# siren_cutdown.net
KiCad netlist of a schematic drawn in EAGLE
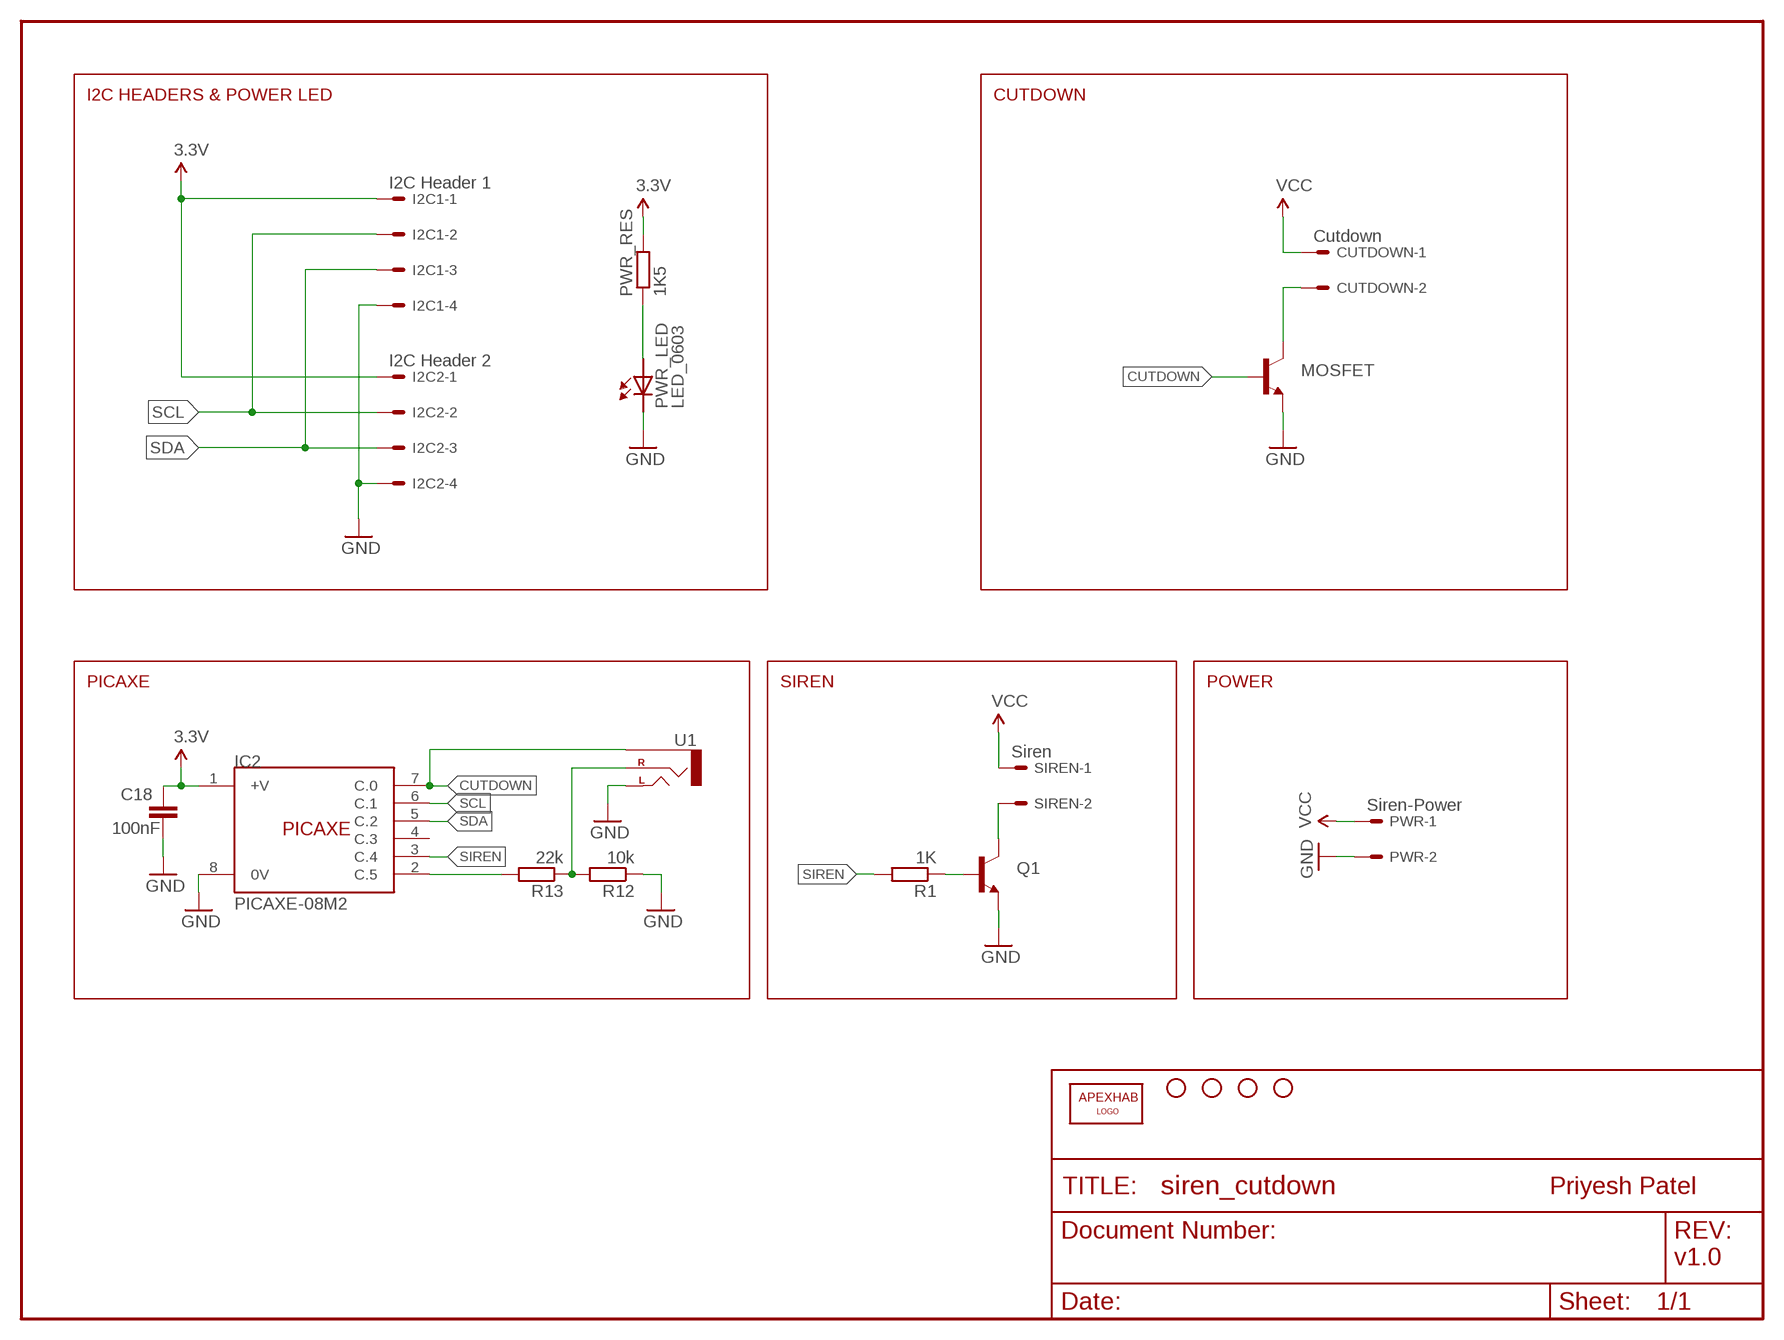
[diagram p0: schematic, sheet 1]

(export (version "E")
  (design (tool "Eeschema 10.0.6"))
  (components
    (comp (ref "C18")
      (value "100nF")
      (footprint "eagle-import:C0805")
      (libsource (lib "eagle-import") (part "C-EUC0805"))
    )
    (comp (ref "CUTDOWN")
      (value "Cutdown")
      (footprint "eagle-import:6410-02")
      (libsource (lib "eagle-import") (part "22-?-0227-2021"))
    )
    (comp (ref "I2C1")
      (value "I2C Header 1")
      (footprint "eagle-import:6410-04")
      (libsource (lib "eagle-import") (part "22-?-0427-2041"))
    )
    (comp (ref "I2C2")
      (value "I2C Header 2")
      (footprint "eagle-import:6410-04")
      (libsource (lib "eagle-import") (part "22-?-0427-2041"))
    )
    (comp (ref "IC2")
      (value "PICAXE-08M2")
      (footprint "eagle-import:SOIC8")
      (libsource (lib "eagle-import") (part "PICAXE-08M2"))
    )
    (comp (ref "JP1")
      (value "APEXHAB-LOGO_APEXHAB-SMALL")
      (footprint "eagle-import:APEXHAB-LOGO-SMALL")
      (libsource (lib "eagle-import") (part "APEXHAB-LOGO_APEXHAB-SMALL"))
    )
    (comp (ref "JP2")
      (value "STAND-OFF")
      (footprint "eagle-import:STAND-OFF")
      (libsource (lib "eagle-import") (part "STAND-OFF"))
    )
    (comp (ref "JP3")
      (value "STAND-OFF")
      (footprint "eagle-import:STAND-OFF")
      (libsource (lib "eagle-import") (part "STAND-OFF"))
    )
    (comp (ref "JP4")
      (value "STAND-OFF")
      (footprint "eagle-import:STAND-OFF")
      (libsource (lib "eagle-import") (part "STAND-OFF"))
    )
    (comp (ref "JP5")
      (value "STAND-OFF")
      (footprint "eagle-import:STAND-OFF")
      (libsource (lib "eagle-import") (part "STAND-OFF"))
    )
    (comp (ref "MOSFET")
      (value "TRANSISTOR_NPNSOT23")
      (footprint "eagle-import:SOT23")
      (libsource (lib "eagle-import") (part "TRANSISTOR_NPNSOT23"))
    )
    (comp (ref "PWR")
      (value "Siren-Power")
      (footprint "eagle-import:6410-02")
      (libsource (lib "eagle-import") (part "22-?-0227-2021"))
    )
    (comp (ref "PWR_LED")
      (value "LED_0603")
      (footprint "eagle-import:CHIPLED_0603")
      (libsource (lib "eagle-import") (part "LED_0603"))
    )
    (comp (ref "PWR_RES")
      (value "1K5")
      (footprint "eagle-import:R0805")
      (libsource (lib "eagle-import") (part "R-EU_R0805"))
    )
    (comp (ref "Q1")
      (value "TRANSISTOR_NPN\"")
      (footprint "eagle-import:SOT223")
      (libsource (lib "eagle-import") (part "TRANSISTOR_NPN{dblquote}"))
    )
    (comp (ref "R1")
      (value "1K")
      (footprint "eagle-import:R0805")
      (libsource (lib "eagle-import") (part "R-EU_R0805"))
    )
    (comp (ref "R12")
      (value "10k")
      (footprint "eagle-import:R0805")
      (libsource (lib "eagle-import") (part "R-EU_R0805"))
    )
    (comp (ref "R13")
      (value "22k")
      (footprint "eagle-import:R0805")
      (libsource (lib "eagle-import") (part "R-EU_R0805"))
    )
    (comp (ref "SIREN")
      (value "Siren")
      (footprint "eagle-import:6410-02")
      (libsource (lib "eagle-import") (part "22-?-0227-2021"))
    )
    (comp (ref "U1")
      (value "AUDIO-JACKPTH")
      (footprint "eagle-import:AUDIO-JACK")
      (libsource (lib "eagle-import") (part "AUDIO-JACKPTH"))
    )
  )
  (nets
    (net (code "1") (name "3.3V") (class "Default")
      (node (ref "C18") (pin "1") (pinfunction "1_1") (pintype "passive"))
      (node (ref "I2C1") (pin "1") (pinfunction "S_1") (pintype "passive"))
      (node (ref "I2C2") (pin "1") (pinfunction "S_1") (pintype "passive"))
      (node (ref "IC2") (pin "1") (pinfunction "+V_1") (pintype "power_in"))
      (node (ref "PWR_RES") (pin "2") (pinfunction "2_2") (pintype "passive"))
    )
    (net (code "2") (name "CUTDOWN") (class "Default")
      (node (ref "IC2") (pin "7") (pinfunction "C.0_7") (pintype "bidirectional"))
      (node (ref "MOSFET") (pin "1") (pinfunction "B_1") (pintype "passive"))
      (node (ref "U1") (pin "SLEEVE") (pinfunction "SLEEVE_SLEEVE") (pintype "bidirectional"))
    )
    (net (code "3") (name "GND") (class "Default")
      (node (ref "C18") (pin "2") (pinfunction "2_2") (pintype "passive"))
      (node (ref "I2C1") (pin "4") (pinfunction "S_4") (pintype "passive"))
      (node (ref "I2C2") (pin "4") (pinfunction "S_4") (pintype "passive"))
      (node (ref "IC2") (pin "8") (pinfunction "0V_8") (pintype "power_in"))
      (node (ref "MOSFET") (pin "2") (pinfunction "E_2") (pintype "passive"))
      (node (ref "PWR") (pin "2") (pinfunction "S_2") (pintype "passive"))
      (node (ref "PWR_LED") (pin "C") (pinfunction "C_C") (pintype "passive"))
      (node (ref "Q1") (pin "3") (pinfunction "E_3") (pintype "passive"))
      (node (ref "R12") (pin "1") (pinfunction "1_1") (pintype "passive"))
      (node (ref "U1") (pin "TIP") (pinfunction "LEFT_TIP") (pintype "bidirectional"))
    )
    (net (code "4") (name "Net-(CUTDOWNB-S)") (class "Default")
      (node (ref "CUTDOWN") (pin "2") (pinfunction "S_2") (pintype "passive"))
      (node (ref "MOSFET") (pin "3") (pinfunction "C_3") (pintype "passive"))
    )
    (net (code "5") (name "Net-(IC2-C.5)") (class "Default")
      (node (ref "IC2") (pin "2") (pinfunction "C.5_2") (pintype "bidirectional"))
      (node (ref "R13") (pin "2") (pinfunction "2_2") (pintype "passive"))
    )
    (net (code "6") (name "Net-(PWR_LED-PadA)") (class "Default")
      (node (ref "PWR_LED") (pin "A") (pinfunction "A_A") (pintype "passive"))
      (node (ref "PWR_RES") (pin "1") (pinfunction "1_1") (pintype "passive"))
    )
    (net (code "7") (name "Net-(Q1-B)") (class "Default")
      (node (ref "Q1") (pin "1") (pinfunction "B_1") (pintype "passive"))
      (node (ref "R1") (pin "1") (pinfunction "1_1") (pintype "passive"))
    )
    (net (code "8") (name "Net-(Q1-C)") (class "Default")
      (node (ref "Q1") (pin "2") (pinfunction "C_2") (pintype "passive"))
      (node (ref "SIREN") (pin "2") (pinfunction "S_2") (pintype "passive"))
    )
    (net (code "9") (name "Net-(U1-RIGHT)") (class "Default")
      (node (ref "R12") (pin "2") (pinfunction "2_2") (pintype "passive"))
      (node (ref "R13") (pin "1") (pinfunction "1_1") (pintype "passive"))
      (node (ref "U1") (pin "RING") (pinfunction "RIGHT_RING") (pintype "bidirectional"))
    )
    (net (code "10") (name "SCL") (class "Default")
      (node (ref "I2C1") (pin "2") (pinfunction "S_2") (pintype "passive"))
      (node (ref "I2C2") (pin "2") (pinfunction "S_2") (pintype "passive"))
      (node (ref "IC2") (pin "6") (pinfunction "C.1_6") (pintype "bidirectional"))
    )
    (net (code "11") (name "SDA") (class "Default")
      (node (ref "I2C1") (pin "3") (pinfunction "S_3") (pintype "passive"))
      (node (ref "I2C2") (pin "3") (pinfunction "S_3") (pintype "passive"))
      (node (ref "IC2") (pin "5") (pinfunction "C.2_5") (pintype "bidirectional"))
    )
    (net (code "12") (name "SIREN") (class "Default")
      (node (ref "IC2") (pin "3") (pinfunction "C.4_3") (pintype "bidirectional"))
      (node (ref "R1") (pin "2") (pinfunction "2_2") (pintype "passive"))
    )
    (net (code "13") (name "VCC") (class "Default")
      (node (ref "CUTDOWN") (pin "1") (pinfunction "S_1") (pintype "passive"))
      (node (ref "PWR") (pin "1") (pinfunction "S_1") (pintype "passive"))
      (node (ref "SIREN") (pin "1") (pinfunction "S_1") (pintype "passive"))
    )
    (net (code "14") (name "unconnected-(IC2-C.3-Pad4)") (class "Default")
      (node (ref "IC2") (pin "4") (pinfunction "C.3_4") (pintype "bidirectional"))
    )
  )
)
